# EndEffector2018_19.net
KiCad netlist of a schematic drawn in Altium Designer
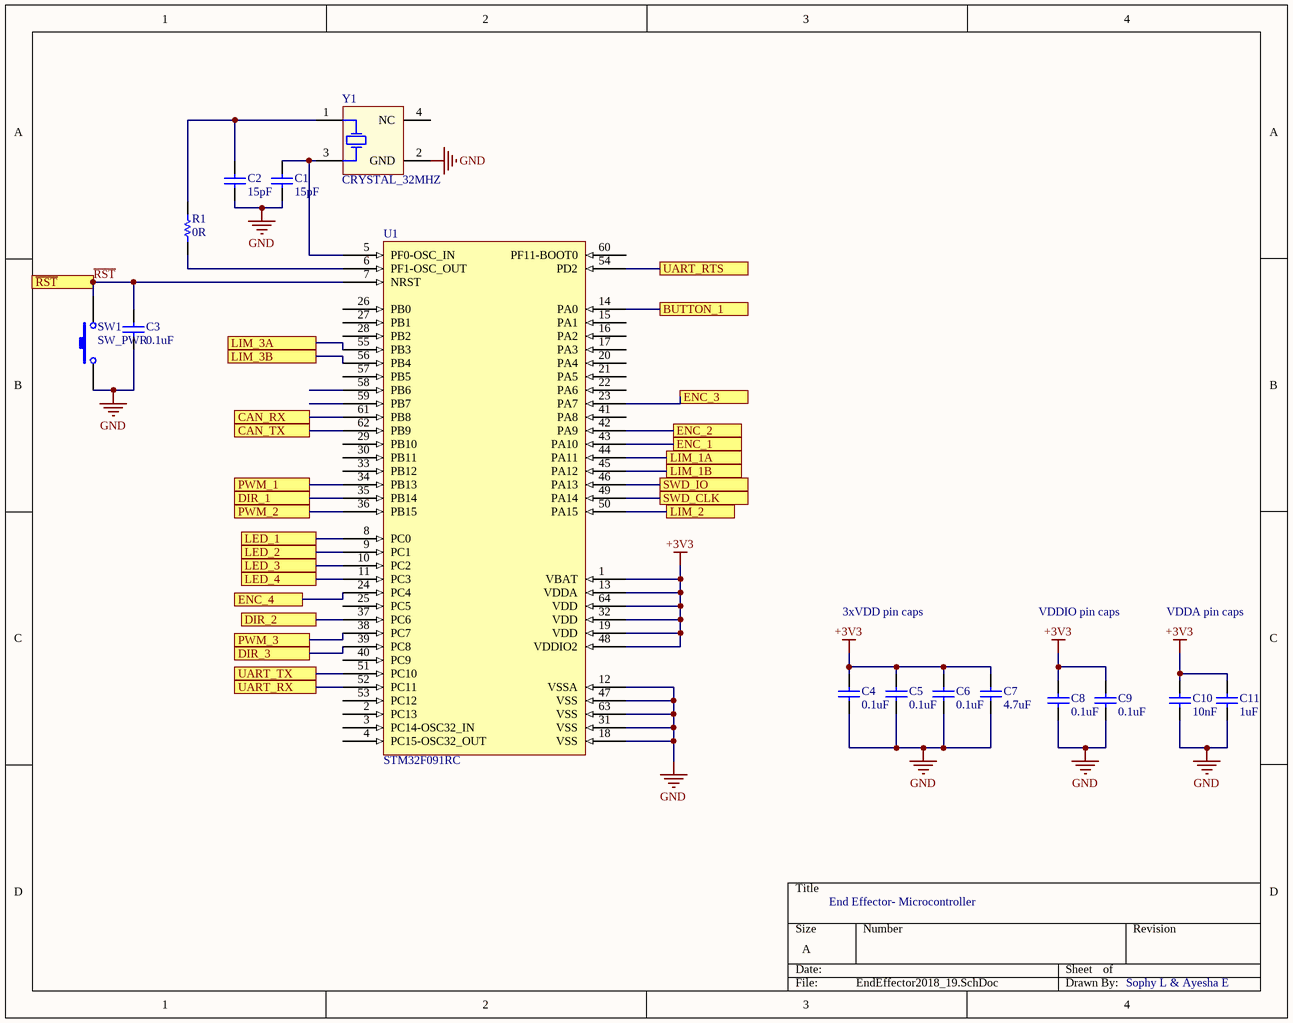
[diagram p0: EndEffector2018_19.SchDoc]

(export (version "E")
  (design (tool "Eeschema 10.0.6"))
  (components
    (comp (ref "C1")
      (value "15pF")
      (footprint "CAPC0603(1608)55_N")
      (description "CAP CER 15PF 250V NPO 0603")
      (fields (field (name "PART NUMBER") "AC0603JRNPOYBN150") (field (name "MANUFACTURER") "Yageo"))
      (libsource (lib "UWRT_Schematic_Library_2019") (part "CAP_15pF_0603"))
    )
    (comp (ref "C2")
      (value "15pF")
      (footprint "CAPC0603(1608)55_N")
      (description "CAP CER 15PF 250V NPO 0603")
      (fields (field (name "PART NUMBER") "AC0603JRNPOYBN150") (field (name "MANUFACTURER") "Yageo"))
      (libsource (lib "UWRT_Schematic_Library_2019") (part "CAP_15pF_0603"))
    )
    (comp (ref "C3")
      (value "0.1uF")
      (footprint "CAPC0603(1608)55_N")
      (description "CAP CER 0.1UF 16V X7R 0603")
      (fields (field (name "PART NUMBER") "CC0603KRX7R7BB104") (field (name "MANUFACTURER") "Yageo"))
      (libsource (lib "UWRT_Schematic_Library_2019") (part "CAP_0.1uF_16V_0603"))
    )
    (comp (ref "C4")
      (value "0.1uF")
      (footprint "CAPC0603(1608)55_N")
      (description "CAP CER 0.1UF 16V X7R 0603")
      (fields (field (name "PART NUMBER") "CC0603KRX7R7BB104") (field (name "MANUFACTURER") "Yageo"))
      (libsource (lib "UWRT_Schematic_Library_2019") (part "CAP_0.1uF_16V_0603"))
    )
    (comp (ref "C5")
      (value "0.1uF")
      (footprint "CAPC0603(1608)55_N")
      (description "CAP CER 0.1UF 16V X7R 0603")
      (fields (field (name "PART NUMBER") "CC0603KRX7R7BB104") (field (name "MANUFACTURER") "Yageo"))
      (libsource (lib "UWRT_Schematic_Library_2019") (part "CAP_0.1uF_16V_0603"))
    )
    (comp (ref "C6")
      (value "0.1uF")
      (footprint "CAPC0603(1608)55_N")
      (description "CAP CER 0.1UF 16V X7R 0603")
      (fields (field (name "PART NUMBER") "CC0603KRX7R7BB104") (field (name "MANUFACTURER") "Yageo"))
      (libsource (lib "UWRT_Schematic_Library_2019") (part "CAP_0.1uF_16V_0603"))
    )
    (comp (ref "C7")
      (value "4.7uF")
      (footprint "CAPC0603(1608)55_N")
      (description "CAP CER 4.7UF 6.3V X5R 0603")
      (fields (field (name "PART NUMBER") "CC0603KRX5R5BB475") (field (name "MANUFACTURER") "Yageo"))
      (libsource (lib "UWRT_Schematic_Library_2019") (part "CAP_4.7uF_0603"))
    )
    (comp (ref "C8")
      (value "0.1uF")
      (footprint "CAPC0603(1608)55_N")
      (description "CAP CER 0.1UF 16V X7R 0603")
      (fields (field (name "PART NUMBER") "CC0603KRX7R7BB104") (field (name "MANUFACTURER") "Yageo"))
      (libsource (lib "UWRT_Schematic_Library_2019") (part "CAP_0.1uF_16V_0603"))
    )
    (comp (ref "C9")
      (value "0.1uF")
      (footprint "CAPC0603(1608)55_N")
      (description "CAP CER 0.1UF 16V X7R 0603")
      (fields (field (name "PART NUMBER") "CC0603KRX7R7BB104") (field (name "MANUFACTURER") "Yageo"))
      (libsource (lib "UWRT_Schematic_Library_2019") (part "CAP_0.1uF_16V_0603"))
    )
    (comp (ref "C10")
      (value "10nF")
      (footprint "CAPC0603(1608)55_N")
      (description "CAP CER 10000PF 16V X7R 0603")
      (fields (field (name "PART NUMBER") "CC0603KRX7R7BB103") (field (name "MANUFACTURER") "Yageo"))
      (libsource (lib "UWRT_Schematic_Library_2019") (part "CAP_10nF_0603"))
    )
    (comp (ref "C11")
      (value "1uF")
      (footprint "CAPC0603(1608)55_N")
      (description "CAP CER 1UF 16V Y5V 0603")
      (fields (field (name "PART NUMBER") "CC0603ZRY5V7BB105") (field (name "MANUFACTURER") "Yageo"))
      (libsource (lib "UWRT_Schematic_Library_2019") (part "CAP_1uF_16V_0603"))
    )
    (comp (ref "R1")
      (value "0R")
      (footprint "RESC0201(0603)_N")
      (description "RES SMD 0 OHM JUMPER 1/10W 0603")
      (fields (field (name "MANUFACTURER") "Yageo") (field (name "Comment") "RES_0R_0603"))
      (libsource (lib "UWRT_Schematic_Library_2019") (part "RES_0R_0603"))
    )
    (comp (ref "SW1")
      (value "SW_PWR")
      (footprint "SPST-2")
      (description "Switch")
      (fields (field (name "PUBLISHER") "Altium Limited"))
      (libsource (lib "UWRT_Schematic_Library_2019") (part "SW_PWR"))
    )
    (comp (ref "U1")
      (value "STM32F091RC")
      (footprint "STM-LQFP64_M")
      (fields (field (name "MANUFACTURER") "STMicroelectronics"))
      (libsource (lib "UWRT_Schematic_Library_2019") (part "STM32F091RC"))
    )
    (comp (ref "Y1")
      (value "CRYSTAL_32MHZ")
      (footprint "AVX-CX2520DB32000D0GEJZ1-4_V")
      (description "CRYSTAL 32MHZ 8PF SMD")
      (fields
        (field (name "PART NUMBER") "CX2520DB32000D0GPSC1")
        (field (name "MANUFACTURER") "Kyocera International Inc. Electronic Components")
      )
      (libsource (lib "UWRT_Schematic_Library_2019") (part "CRYSTAL_32MHZ"))
    )
  )
  (nets
    (net (code "1") (name "+3V3") (class "Default")
      (node (ref "C10") (pin "2") (pinfunction "2_2") (pintype "passive"))
      (node (ref "C11") (pin "2") (pinfunction "2_2") (pintype "passive"))
      (node (ref "C4") (pin "2") (pinfunction "2_2") (pintype "passive"))
      (node (ref "C5") (pin "2") (pinfunction "2_2") (pintype "passive"))
      (node (ref "C6") (pin "2") (pinfunction "2_2") (pintype "passive"))
      (node (ref "C7") (pin "2") (pinfunction "2_2") (pintype "passive"))
      (node (ref "C8") (pin "2") (pinfunction "2_2") (pintype "passive"))
      (node (ref "C9") (pin "2") (pinfunction "2_2") (pintype "passive"))
      (node (ref "U1") (pin "1") (pinfunction "VBAT_1") (pintype "input"))
      (node (ref "U1") (pin "13") (pinfunction "VDDA_13") (pintype "input"))
      (node (ref "U1") (pin "19") (pinfunction "VDD_19") (pintype "input"))
      (node (ref "U1") (pin "32") (pinfunction "VDD_32") (pintype "input"))
      (node (ref "U1") (pin "48") (pinfunction "VDDIO2_48") (pintype "input"))
      (node (ref "U1") (pin "64") (pinfunction "VDD_64") (pintype "input"))
    )
    (net (code "2") (name "/BUTTON_1") (class "Default")
      (node (ref "U1") (pin "14") (pinfunction "PA0_14") (pintype "input"))
    )
    (net (code "3") (name "/CAN_RX") (class "Default")
      (node (ref "U1") (pin "61") (pinfunction "PB8_61") (pintype "input"))
    )
    (net (code "4") (name "/CAN_TX") (class "Default")
      (node (ref "U1") (pin "62") (pinfunction "PB9_62") (pintype "input"))
    )
    (net (code "5") (name "/DIR_1") (class "Default")
      (node (ref "U1") (pin "35") (pinfunction "PB14_35") (pintype "input"))
    )
    (net (code "6") (name "/DIR_2") (class "Default")
      (node (ref "U1") (pin "37") (pinfunction "PC6_37") (pintype "input"))
    )
    (net (code "7") (name "/DIR_3") (class "Default")
      (node (ref "U1") (pin "39") (pinfunction "PC8_39") (pintype "input"))
    )
    (net (code "8") (name "/ENC_1") (class "Default")
      (node (ref "U1") (pin "43") (pinfunction "PA10_43") (pintype "input"))
    )
    (net (code "9") (name "/ENC_2") (class "Default")
      (node (ref "U1") (pin "42") (pinfunction "PA9_42") (pintype "input"))
    )
    (net (code "10") (name "/ENC_3") (class "Default")
      (node (ref "U1") (pin "23") (pinfunction "PA7_23") (pintype "input"))
    )
    (net (code "11") (name "/ENC_4") (class "Default")
      (node (ref "U1") (pin "24") (pinfunction "PC4_24") (pintype "input"))
    )
    (net (code "12") (name "/LED_1") (class "Default")
      (node (ref "U1") (pin "8") (pinfunction "PC0_8") (pintype "input"))
    )
    (net (code "13") (name "/LED_2") (class "Default")
      (node (ref "U1") (pin "9") (pinfunction "PC1_9") (pintype "input"))
    )
    (net (code "14") (name "/LED_3") (class "Default")
      (node (ref "U1") (pin "10") (pinfunction "PC2_10") (pintype "input"))
    )
    (net (code "15") (name "/LED_4") (class "Default")
      (node (ref "U1") (pin "11") (pinfunction "PC3_11") (pintype "input"))
    )
    (net (code "16") (name "/LIM_1A") (class "Default")
      (node (ref "U1") (pin "44") (pinfunction "PA11_44") (pintype "input"))
    )
    (net (code "17") (name "/LIM_1B") (class "Default")
      (node (ref "U1") (pin "45") (pinfunction "PA12_45") (pintype "input"))
    )
    (net (code "18") (name "/LIM_2") (class "Default")
      (node (ref "U1") (pin "50") (pinfunction "PA15_50") (pintype "input"))
    )
    (net (code "19") (name "/LIM_3A") (class "Default")
      (node (ref "U1") (pin "55") (pinfunction "PB3_55") (pintype "input"))
    )
    (net (code "20") (name "/LIM_3B") (class "Default")
      (node (ref "U1") (pin "56") (pinfunction "PB4_56") (pintype "input"))
    )
    (net (code "21") (name "/PWM_1") (class "Default")
      (node (ref "U1") (pin "34") (pinfunction "PB13_34") (pintype "input"))
    )
    (net (code "22") (name "/PWM_2") (class "Default")
      (node (ref "U1") (pin "36") (pinfunction "PB15_36") (pintype "input"))
    )
    (net (code "23") (name "/PWM_3") (class "Default")
      (node (ref "U1") (pin "38") (pinfunction "PC7_38") (pintype "input"))
    )
    (net (code "24") (name "/SWD_CLK") (class "Default")
      (node (ref "U1") (pin "49") (pinfunction "PA14_49") (pintype "input"))
    )
    (net (code "25") (name "/SWD_IO") (class "Default")
      (node (ref "U1") (pin "46") (pinfunction "PA13_46") (pintype "input"))
    )
    (net (code "26") (name "/UART_RTS") (class "Default")
      (node (ref "U1") (pin "54") (pinfunction "PD2_54") (pintype "input"))
    )
    (net (code "27") (name "/UART_RX") (class "Default")
      (node (ref "U1") (pin "52") (pinfunction "PC11_52") (pintype "input"))
    )
    (net (code "28") (name "/UART_TX") (class "Default")
      (node (ref "U1") (pin "51") (pinfunction "PC10_51") (pintype "input"))
    )
    (net (code "29") (name "/~{RST}") (class "Default")
      (node (ref "C3") (pin "2") (pinfunction "2_2") (pintype "passive"))
      (node (ref "SW1") (pin "2") (pinfunction "2_2") (pintype "passive"))
      (node (ref "U1") (pin "7") (pinfunction "NRST_7") (pintype "input"))
    )
    (net (code "30") (name "GND") (class "Default")
      (node (ref "C1") (pin "1") (pinfunction "1_1") (pintype "passive"))
      (node (ref "C10") (pin "1") (pinfunction "1_1") (pintype "passive"))
      (node (ref "C11") (pin "1") (pinfunction "1_1") (pintype "passive"))
      (node (ref "C2") (pin "1") (pinfunction "1_1") (pintype "passive"))
      (node (ref "C3") (pin "1") (pinfunction "1_1") (pintype "passive"))
      (node (ref "C4") (pin "1") (pinfunction "1_1") (pintype "passive"))
      (node (ref "C5") (pin "1") (pinfunction "1_1") (pintype "passive"))
      (node (ref "C6") (pin "1") (pinfunction "1_1") (pintype "passive"))
      (node (ref "C7") (pin "1") (pinfunction "1_1") (pintype "passive"))
      (node (ref "C8") (pin "1") (pinfunction "1_1") (pintype "passive"))
      (node (ref "C9") (pin "1") (pinfunction "1_1") (pintype "passive"))
      (node (ref "SW1") (pin "1") (pinfunction "1_1") (pintype "passive"))
      (node (ref "U1") (pin "12") (pinfunction "VSSA_12") (pintype "input"))
      (node (ref "U1") (pin "18") (pinfunction "VSS_18") (pintype "input"))
      (node (ref "U1") (pin "31") (pinfunction "VSS_31") (pintype "input"))
      (node (ref "U1") (pin "47") (pinfunction "VSS_47") (pintype "input"))
      (node (ref "U1") (pin "63") (pinfunction "VSS_63") (pintype "input"))
      (node (ref "Y1") (pin "2") (pinfunction "GND_2") (pintype "power_in"))
    )
    (net (code "31") (name "Net-(C2-Pad2)") (class "Default")
      (node (ref "C2") (pin "2") (pinfunction "2_2") (pintype "passive"))
      (node (ref "R1") (pin "2") (pinfunction "2_2") (pintype "passive"))
      (node (ref "Y1") (pin "1") (pinfunction "HOT_1") (pintype "passive"))
    )
    (net (code "32") (name "Net-(U1-PF0-OSC_IN)") (class "Default")
      (node (ref "C1") (pin "2") (pinfunction "2_2") (pintype "passive"))
      (node (ref "U1") (pin "5") (pinfunction "PF0-OSC_IN_5") (pintype "input"))
      (node (ref "Y1") (pin "3") (pinfunction "HOT_3") (pintype "passive"))
    )
    (net (code "33") (name "Net-(U1-PF1-OSC_OUT)") (class "Default")
      (node (ref "R1") (pin "1") (pinfunction "1_1") (pintype "passive"))
      (node (ref "U1") (pin "6") (pinfunction "PF1-OSC_OUT_6") (pintype "input"))
    )
    (net (code "34") (name "unconnected-(U1-PA1-Pad15)") (class "Default")
      (node (ref "U1") (pin "15") (pinfunction "PA1_15") (pintype "input"))
    )
    (net (code "35") (name "unconnected-(U1-PA2-Pad16)") (class "Default")
      (node (ref "U1") (pin "16") (pinfunction "PA2_16") (pintype "input"))
    )
    (net (code "36") (name "unconnected-(U1-PA3-Pad17)") (class "Default")
      (node (ref "U1") (pin "17") (pinfunction "PA3_17") (pintype "input"))
    )
    (net (code "37") (name "unconnected-(U1-PA4-Pad20)") (class "Default")
      (node (ref "U1") (pin "20") (pinfunction "PA4_20") (pintype "input"))
    )
    (net (code "38") (name "unconnected-(U1-PA5-Pad21)") (class "Default")
      (node (ref "U1") (pin "21") (pinfunction "PA5_21") (pintype "input"))
    )
    (net (code "39") (name "unconnected-(U1-PA6-Pad22)") (class "Default")
      (node (ref "U1") (pin "22") (pinfunction "PA6_22") (pintype "input"))
    )
    (net (code "40") (name "unconnected-(U1-PA8-Pad41)") (class "Default")
      (node (ref "U1") (pin "41") (pinfunction "PA8_41") (pintype "input"))
    )
    (net (code "41") (name "unconnected-(U1-PB0-Pad26)") (class "Default")
      (node (ref "U1") (pin "26") (pinfunction "PB0_26") (pintype "input"))
    )
    (net (code "42") (name "unconnected-(U1-PB1-Pad27)") (class "Default")
      (node (ref "U1") (pin "27") (pinfunction "PB1_27") (pintype "input"))
    )
    (net (code "43") (name "unconnected-(U1-PB2-Pad28)") (class "Default")
      (node (ref "U1") (pin "28") (pinfunction "PB2_28") (pintype "input"))
    )
    (net (code "44") (name "unconnected-(U1-PB5-Pad57)") (class "Default")
      (node (ref "U1") (pin "57") (pinfunction "PB5_57") (pintype "input"))
    )
    (net (code "45") (name "unconnected-(U1-PB6-Pad58)") (class "Default")
      (node (ref "U1") (pin "58") (pinfunction "PB6_58") (pintype "input"))
    )
    (net (code "46") (name "unconnected-(U1-PB7-Pad59)") (class "Default")
      (node (ref "U1") (pin "59") (pinfunction "PB7_59") (pintype "input"))
    )
    (net (code "47") (name "unconnected-(U1-PB10-Pad29)") (class "Default")
      (node (ref "U1") (pin "29") (pinfunction "PB10_29") (pintype "input"))
    )
    (net (code "48") (name "unconnected-(U1-PB11-Pad30)") (class "Default")
      (node (ref "U1") (pin "30") (pinfunction "PB11_30") (pintype "input"))
    )
    (net (code "49") (name "unconnected-(U1-PB12-Pad33)") (class "Default")
      (node (ref "U1") (pin "33") (pinfunction "PB12_33") (pintype "input"))
    )
    (net (code "50") (name "unconnected-(U1-PC5-Pad25)") (class "Default")
      (node (ref "U1") (pin "25") (pinfunction "PC5_25") (pintype "input"))
    )
    (net (code "51") (name "unconnected-(U1-PC9-Pad40)") (class "Default")
      (node (ref "U1") (pin "40") (pinfunction "PC9_40") (pintype "input"))
    )
    (net (code "52") (name "unconnected-(U1-PC12-Pad53)") (class "Default")
      (node (ref "U1") (pin "53") (pinfunction "PC12_53") (pintype "input"))
    )
    (net (code "53") (name "unconnected-(U1-PC13-Pad2)") (class "Default")
      (node (ref "U1") (pin "2") (pinfunction "PC13_2") (pintype "input"))
    )
    (net (code "54") (name "unconnected-(U1-PC14-OSC32_IN-Pad3)") (class "Default")
      (node (ref "U1") (pin "3") (pinfunction "PC14-OSC32_IN_3") (pintype "input"))
    )
    (net (code "55") (name "unconnected-(U1-PC15-OSC32_OUT-Pad4)") (class "Default")
      (node (ref "U1") (pin "4") (pinfunction "PC15-OSC32_OUT_4") (pintype "input"))
    )
    (net (code "56") (name "unconnected-(U1-PF11-BOOT0-Pad60)") (class "Default")
      (node (ref "U1") (pin "60") (pinfunction "PF11-BOOT0_60") (pintype "input"))
    )
    (net (code "57") (name "unconnected-(Y1-NC-Pad4)") (class "Default")
      (node (ref "Y1") (pin "4") (pinfunction "NC_4") (pintype "passive"))
    )
  )
)
